# BSPD_Test_Board_rev5.net
KiCad netlist of a schematic drawn in EAGLE
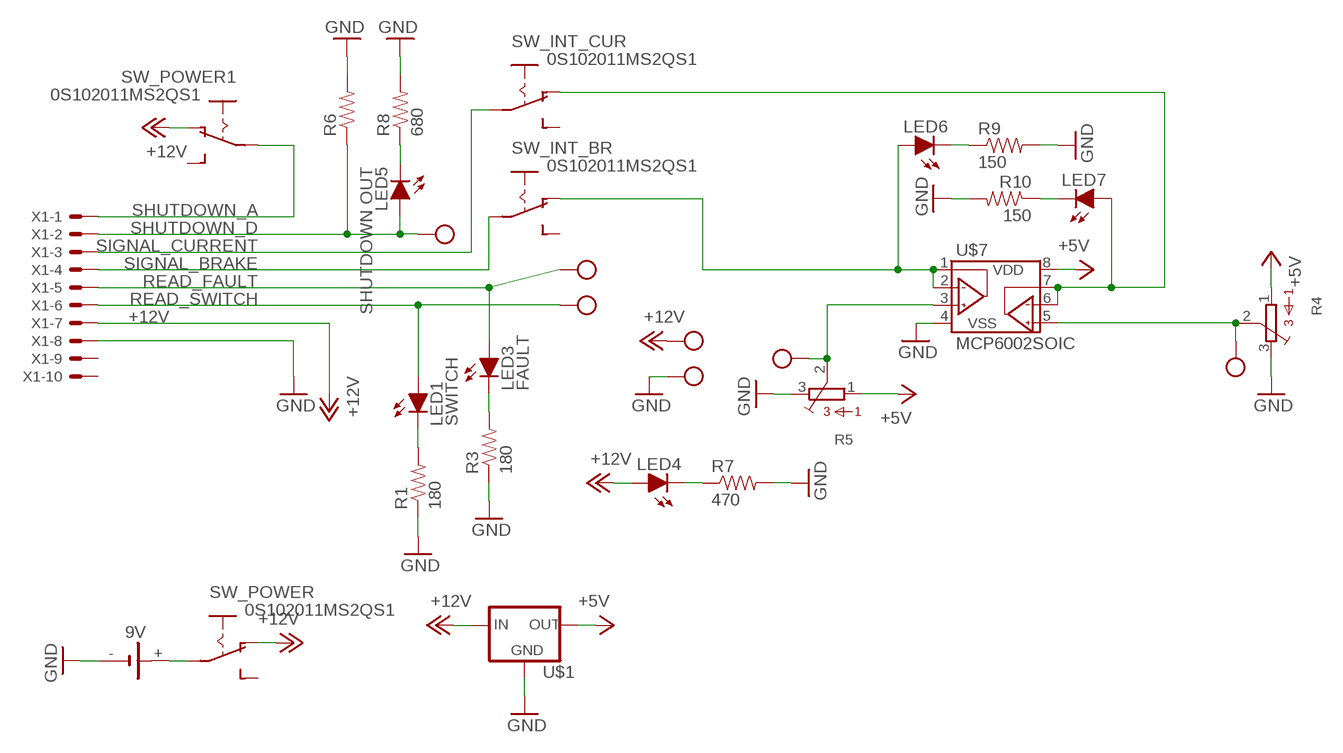
[diagram p0: schematic, sheet 1]

(export (version "E")
  (design (tool "Eeschema 10.0.6"))
  (components
    (comp (ref "9V")
      (value "1291-79")
      (footprint "eagle-import:1291-79")
      (libsource (lib "eagle-import") (part "1291-79"))
    )
    (comp (ref "LED1")
      (value "SWITCH")
      (footprint "eagle-import:LED-5MM")
      (libsource (lib "eagle-import") (part "LED-5MM"))
    )
    (comp (ref "LED3")
      (value "FAULT")
      (footprint "eagle-import:LED-5MM")
      (libsource (lib "eagle-import") (part "LED-5MM"))
    )
    (comp (ref "LED4")
      (value "LED-0805")
      (footprint "eagle-import:LED-805")
      (libsource (lib "eagle-import") (part "LED-0805"))
    )
    (comp (ref "LED5")
      (value "SHUTDOWN OUT")
      (footprint "eagle-import:LED-5MM")
      (libsource (lib "eagle-import") (part "LED-5MM"))
    )
    (comp (ref "LED6")
      (value "LED-0805")
      (footprint "eagle-import:LED-805")
      (libsource (lib "eagle-import") (part "LED-0805"))
    )
    (comp (ref "LED7")
      (value "LED-0805")
      (footprint "eagle-import:LED-805")
      (libsource (lib "eagle-import") (part "LED-0805"))
    )
    (comp (ref "R1")
      (value "180")
      (footprint "eagle-import:0805")
      (libsource (lib "eagle-import") (part "RESISTOR0805-RES"))
    )
    (comp (ref "R3")
      (value "180")
      (footprint "eagle-import:0805")
      (libsource (lib "eagle-import") (part "RESISTOR0805-RES"))
    )
    (comp (ref "R4")
      (value "TRIMPOT_3296C")
      (footprint "eagle-import:TRIMPOT_3296")
      (libsource (lib "eagle-import") (part "TRIMPOT_3296C"))
    )
    (comp (ref "R5")
      (value "TRIMPOT_3296C")
      (footprint "eagle-import:TRIMPOT_3296")
      (libsource (lib "eagle-import") (part "TRIMPOT_3296C"))
    )
    (comp (ref "R6")
      (value "RESISTORPTH-1/2W")
      (footprint "eagle-import:AXIAL-0.5")
      (libsource (lib "eagle-import") (part "RESISTORPTH-1/2W"))
    )
    (comp (ref "R7")
      (value "470")
      (footprint "eagle-import:0805")
      (libsource (lib "eagle-import") (part "RESISTOR0805-RES"))
    )
    (comp (ref "R8")
      (value "680")
      (footprint "eagle-import:0805")
      (libsource (lib "eagle-import") (part "RESISTOR0805-RES"))
    )
    (comp (ref "R9")
      (value "150")
      (footprint "eagle-import:0805")
      (libsource (lib "eagle-import") (part "RESISTOR0805-RES"))
    )
    (comp (ref "R10")
      (value "150")
      (footprint "eagle-import:0805")
      (libsource (lib "eagle-import") (part "RESISTOR0805-RES"))
    )
    (comp (ref "SW_INT_BR")
      (value "0S102011MS2QS1")
      (footprint "eagle-import:0S102011MS2QS1")
      (libsource (lib "eagle-import") (part "0S102011MS2QS1"))
    )
    (comp (ref "SW_INT_CUR")
      (value "0S102011MS2QS1")
      (footprint "eagle-import:0S102011MS2QS1")
      (libsource (lib "eagle-import") (part "0S102011MS2QS1"))
    )
    (comp (ref "SW_POWER")
      (value "0S102011MS2QS1")
      (footprint "eagle-import:0S102011MS2QS1")
      (libsource (lib "eagle-import") (part "0S102011MS2QS1"))
    )
    (comp (ref "SW_POWER1")
      (value "0S102011MS2QS1")
      (footprint "eagle-import:0S102011MS2QS1")
      (libsource (lib "eagle-import") (part "0S102011MS2QS1"))
    )
    (comp (ref "U$1")
      (value "5VREG_LM340-NLM340MPX-5.0/NOPB")
      (footprint "eagle-import:SOT223")
      (libsource (lib "eagle-import") (part "5VREG_LM340-NLM340MPX-5.0/NOPB"))
    )
    (comp (ref "U$2")
      (value "TEST_POINT")
      (footprint "eagle-import:TEST_POINT")
      (libsource (lib "eagle-import") (part "TEST_POINT"))
    )
    (comp (ref "U$3")
      (value "TEST_POINT")
      (footprint "eagle-import:TEST_POINT")
      (libsource (lib "eagle-import") (part "TEST_POINT"))
    )
    (comp (ref "U$4")
      (value "TEST_POINT")
      (footprint "eagle-import:TEST_POINT")
      (libsource (lib "eagle-import") (part "TEST_POINT"))
    )
    (comp (ref "U$5")
      (value "TEST_POINT")
      (footprint "eagle-import:TEST_POINT")
      (libsource (lib "eagle-import") (part "TEST_POINT"))
    )
    (comp (ref "U$6")
      (value "TEST_POINT")
      (footprint "eagle-import:TEST_POINT")
      (libsource (lib "eagle-import") (part "TEST_POINT"))
    )
    (comp (ref "U$7")
      (value "MCP6002SOIC")
      (footprint "eagle-import:SOIC-08")
      (libsource (lib "eagle-import") (part "MCP6002SOIC"))
    )
    (comp (ref "U$8")
      (value "TEST_POINT")
      (footprint "eagle-import:TEST_POINT")
      (libsource (lib "eagle-import") (part "TEST_POINT"))
    )
    (comp (ref "U$10")
      (value "TEST_POINT")
      (footprint "eagle-import:TEST_POINT")
      (libsource (lib "eagle-import") (part "TEST_POINT"))
    )
    (comp (ref "X1")
      (value "CONNECTOR-10")
      (footprint "eagle-import:MINIFIT_5566-10")
      (libsource (lib "eagle-import") (part "CONNECTOR-10"))
    )
  )
  (nets
    (net (code "1") (name "+5V") (class "Default")
      (node (ref "R4") (pin "1") (pinfunction "1_1") (pintype "passive"))
      (node (ref "R5") (pin "1") (pinfunction "1_1") (pintype "passive"))
      (node (ref "U$1") (pin "3") (pinfunction "OUT_3") (pintype "output"))
      (node (ref "U$7") (pin "8") (pinfunction "VDD_8") (pintype "passive"))
    )
    (net (code "2") (name "+12V") (class "Default")
      (node (ref "LED4") (pin "A") (pinfunction "A_A") (pintype "passive"))
      (node (ref "SW_POWER") (pin "P$1") (pinfunction "O_P$1") (pintype "passive"))
      (node (ref "SW_POWER1") (pin "P$1") (pinfunction "O_P$1") (pintype "passive"))
      (node (ref "U$1") (pin "1") (pinfunction "IN_1") (pintype "input"))
      (node (ref "U$5") (pin "P$1") (pinfunction "P$1_P$1") (pintype "bidirectional"))
      (node (ref "X1") (pin "7") (pinfunction "S_7") (pintype "passive"))
    )
    (net (code "3") (name "/READ_FAULT") (class "Default")
      (node (ref "LED3") (pin "A") (pinfunction "A_A") (pintype "passive"))
      (node (ref "U$8") (pin "P$1") (pinfunction "P$1_P$1") (pintype "bidirectional"))
      (node (ref "X1") (pin "5") (pinfunction "S_5") (pintype "passive"))
    )
    (net (code "4") (name "/READ_SWITCH") (class "Default")
      (node (ref "LED1") (pin "A") (pinfunction "A_A") (pintype "passive"))
      (node (ref "U$10") (pin "P$1") (pinfunction "P$1_P$1") (pintype "bidirectional"))
      (node (ref "X1") (pin "6") (pinfunction "S_6") (pintype "passive"))
    )
    (net (code "5") (name "/SHUTDOWN_D") (class "Default")
      (node (ref "LED5") (pin "A") (pinfunction "A_A") (pintype "passive"))
      (node (ref "R6") (pin "P$1") (pinfunction "1_P$1") (pintype "passive"))
      (node (ref "U$4") (pin "P$1") (pinfunction "P$1_P$1") (pintype "bidirectional"))
      (node (ref "X1") (pin "2") (pinfunction "S_2") (pintype "passive"))
    )
    (net (code "6") (name "/SIGNAL_BRAKE") (class "Default")
      (node (ref "SW_INT_BR") (pin "P$2") (pinfunction "P_P$2") (pintype "passive"))
      (node (ref "X1") (pin "4") (pinfunction "S_4") (pintype "passive"))
    )
    (net (code "7") (name "/SIGNAL_CURRENT") (class "Default")
      (node (ref "SW_INT_CUR") (pin "P$2") (pinfunction "P_P$2") (pintype "passive"))
      (node (ref "X1") (pin "3") (pinfunction "S_3") (pintype "passive"))
    )
    (net (code "8") (name "GND") (class "Default")
      (node (ref "9V") (pin "-") (pinfunction "-_-") (pintype "passive"))
      (node (ref "R1") (pin "1") (pinfunction "1_1") (pintype "passive"))
      (node (ref "R10") (pin "2") (pinfunction "2_2") (pintype "passive"))
      (node (ref "R3") (pin "1") (pinfunction "1_1") (pintype "passive"))
      (node (ref "R4") (pin "3") (pinfunction "3_3") (pintype "passive"))
      (node (ref "R5") (pin "3") (pinfunction "3_3") (pintype "passive"))
      (node (ref "R6") (pin "P$2") (pinfunction "2_P$2") (pintype "passive"))
      (node (ref "R7") (pin "2") (pinfunction "2_2") (pintype "passive"))
      (node (ref "R8") (pin "2") (pinfunction "2_2") (pintype "passive"))
      (node (ref "R9") (pin "2") (pinfunction "2_2") (pintype "passive"))
      (node (ref "U$1") (pin "2") (pinfunction "GND_2") (pintype "input"))
      (node (ref "U$1") (pin "4") (pinfunction "GND_4") (pintype "input"))
      (node (ref "U$6") (pin "P$1") (pinfunction "P$1_P$1") (pintype "bidirectional"))
      (node (ref "U$7") (pin "4") (pinfunction "VSS_4") (pintype "passive"))
      (node (ref "X1") (pin "8") (pinfunction "S_8") (pintype "passive"))
    )
    (net (code "9") (name "Net-(LED1-C)") (class "Default")
      (node (ref "LED1") (pin "K") (pinfunction "C_K") (pintype "passive"))
      (node (ref "R1") (pin "2") (pinfunction "2_2") (pintype "passive"))
    )
    (net (code "10") (name "Net-(LED3-C)") (class "Default")
      (node (ref "LED3") (pin "K") (pinfunction "C_K") (pintype "passive"))
      (node (ref "R3") (pin "2") (pinfunction "2_2") (pintype "passive"))
    )
    (net (code "11") (name "Net-(LED4-PadC)") (class "Default")
      (node (ref "LED4") (pin "C") (pinfunction "C_C") (pintype "passive"))
      (node (ref "R7") (pin "1") (pinfunction "1_1") (pintype "passive"))
    )
    (net (code "12") (name "Net-(LED5-C)") (class "Default")
      (node (ref "LED5") (pin "K") (pinfunction "C_K") (pintype "passive"))
      (node (ref "R8") (pin "1") (pinfunction "1_1") (pintype "passive"))
    )
    (net (code "13") (name "Net-(LED6-PadC)") (class "Default")
      (node (ref "LED6") (pin "C") (pinfunction "C_C") (pintype "passive"))
      (node (ref "R9") (pin "1") (pinfunction "1_1") (pintype "passive"))
    )
    (net (code "14") (name "Net-(LED7-PadC)") (class "Default")
      (node (ref "LED7") (pin "C") (pinfunction "C_C") (pintype "passive"))
      (node (ref "R10") (pin "1") (pinfunction "1_1") (pintype "passive"))
    )
    (net (code "15") (name "Net-(SW_INT_BR-O)") (class "Default")
      (node (ref "LED6") (pin "A") (pinfunction "A_A") (pintype "passive"))
      (node (ref "SW_INT_BR") (pin "P$1") (pinfunction "O_P$1") (pintype "passive"))
      (node (ref "U$7") (pin "1") (pinfunction "VOUTA_1") (pintype "passive"))
      (node (ref "U$7") (pin "2") (pinfunction "VINA-_2") (pintype "passive"))
    )
    (net (code "16") (name "Net-(SW_INT_CUR-O)") (class "Default")
      (node (ref "LED7") (pin "A") (pinfunction "A_A") (pintype "passive"))
      (node (ref "SW_INT_CUR") (pin "P$1") (pinfunction "O_P$1") (pintype "passive"))
      (node (ref "U$7") (pin "6") (pinfunction "VINB-_6") (pintype "passive"))
      (node (ref "U$7") (pin "7") (pinfunction "VOUTB_7") (pintype "passive"))
    )
    (net (code "17") (name "Net-(SW_POWER-P)") (class "Default")
      (node (ref "9V") (pin "+") (pinfunction "+_+") (pintype "passive"))
      (node (ref "SW_POWER") (pin "P$2") (pinfunction "P_P$2") (pintype "passive"))
    )
    (net (code "18") (name "Net-(SW_POWER1-P)") (class "Default")
      (node (ref "SW_POWER1") (pin "P$2") (pinfunction "P_P$2") (pintype "passive"))
      (node (ref "X1") (pin "1") (pinfunction "S_1") (pintype "passive"))
    )
    (net (code "19") (name "Net-(U$7-VINA+)") (class "Default")
      (node (ref "R5") (pin "2") (pinfunction "2_2") (pintype "passive"))
      (node (ref "U$3") (pin "P$1") (pinfunction "P$1_P$1") (pintype "bidirectional"))
      (node (ref "U$7") (pin "3") (pinfunction "VINA+_3") (pintype "passive"))
    )
    (net (code "20") (name "Net-(U$7-VINB+)") (class "Default")
      (node (ref "R4") (pin "2") (pinfunction "2_2") (pintype "passive"))
      (node (ref "U$2") (pin "P$1") (pinfunction "P$1_P$1") (pintype "bidirectional"))
      (node (ref "U$7") (pin "5") (pinfunction "VINB+_5") (pintype "passive"))
    )
    (net (code "21") (name "unconnected-(SW_INT_BR-S-PadP$3)") (class "Default")
      (node (ref "SW_INT_BR") (pin "P$3") (pinfunction "S_P$3") (pintype "passive"))
    )
    (net (code "22") (name "unconnected-(SW_INT_CUR-S-PadP$3)") (class "Default")
      (node (ref "SW_INT_CUR") (pin "P$3") (pinfunction "S_P$3") (pintype "passive"))
    )
    (net (code "23") (name "unconnected-(SW_POWER-S-PadP$3)") (class "Default")
      (node (ref "SW_POWER") (pin "P$3") (pinfunction "S_P$3") (pintype "passive"))
    )
    (net (code "24") (name "unconnected-(SW_POWER1-S-PadP$3)") (class "Default")
      (node (ref "SW_POWER1") (pin "P$3") (pinfunction "S_P$3") (pintype "passive"))
    )
    (net (code "25") (name "unconnected-(X1B-S-Pad10)") (class "Default")
      (node (ref "X1") (pin "10") (pinfunction "S_10") (pintype "passive"))
    )
    (net (code "26") (name "unconnected-(X1J-S-Pad9)") (class "Default")
      (node (ref "X1") (pin "9") (pinfunction "S_9") (pintype "passive"))
    )
  )
)
